# SchematicTensometr.net
KiCad netlist of a schematic drawn in Altium Designer
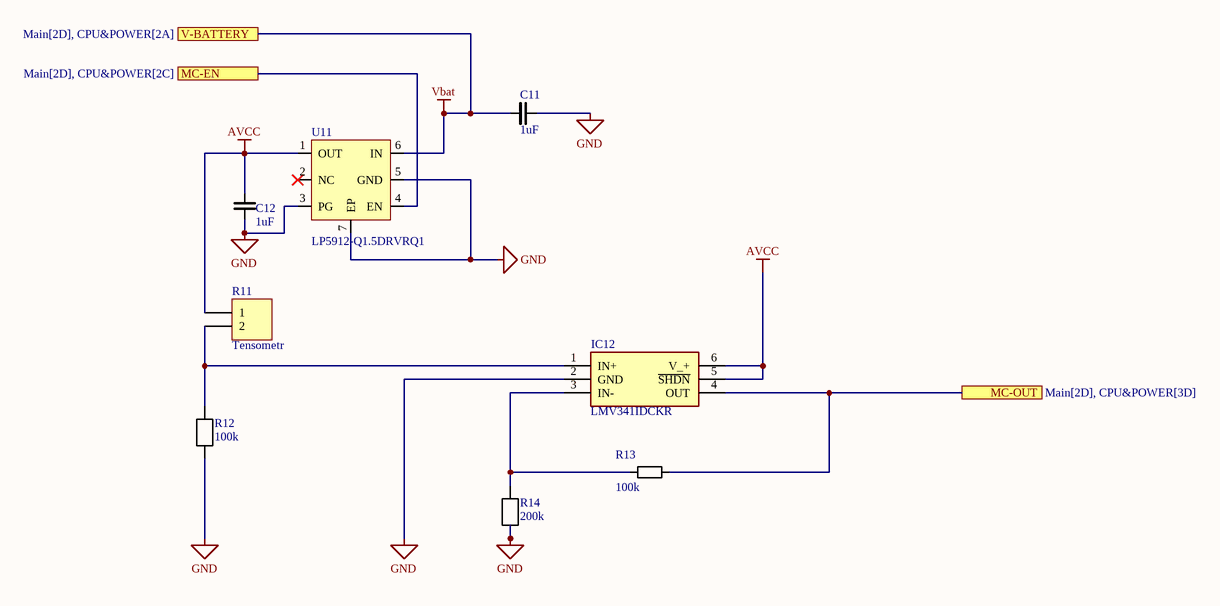
[diagram p0: SchematicTensometr.SchDoc]

(export (version "E")
  (design (tool "Eeschema 10.0.6"))
  (components
    (comp (ref "C11")
      (value "1uF")
      (footprint "0402_CAP")
      (description "Ceramic capacitor")
      (libsource (lib "Cap") (part "Cap"))
    )
    (comp (ref "C12")
      (value "1uF")
      (footprint "0402_CAP")
      (description "Ceramic capacitor")
      (libsource (lib "") (part "Cap_1"))
    )
    (comp (ref "IC12")
      (value "LMV341IDCKR")
      (footprint "SOT65P210X110-6N_m")
      (description "Integrated Circuit")
      (fields (field (name "MOUSER PART NUMBER") "595-LMV341IDCKR"))
      (libsource (lib "*") (part "LMV341IDCKR"))
    )
    (comp (ref "R11")
      (value "Tensometr")
      (footprint "HDR1X2")
      (description "Header, 2-Pin")
      (fields (field (name "PUBLISHER") "Altium Limited"))
      (libsource (lib "Miscellaneous Connectors") (part "Header 2"))
    )
    (comp (ref "R12") (value "100k") (footprint "0402_RES") (libsource (lib "Zad1") (part "Resistor")))
    (comp (ref "R13")
      (value "100k")
      (footprint "0402_RES")
      (description "Resistor")
      (libsource (lib "RES") (part "RES"))
    )
    (comp (ref "R14") (value "200k") (footprint "0402_RES") (libsource (lib "Zad1") (part "Resistor")))
    (comp (ref "U11")
      (value "LP5912-Q1.5DRVRQ1")
      (footprint "SON65P200X200X80-7N_m")
      (libsource (lib "parts1") (part "STAB"))
    )
  )
  (nets
    (net (code "1") (name "/MC-EN") (class "Default")
      (node (ref "U11") (pin "4") (pinfunction "EN_4") (pintype "passive"))
    )
    (net (code "2") (name "/MC-OUT") (class "Default")
      (node (ref "IC12") (pin "4") (pinfunction "OUT_4") (pintype "passive"))
      (node (ref "R13") (pin "2") (pinfunction "2_2") (pintype "passive"))
    )
    (net (code "3") (name "AVCC") (class "Default")
      (node (ref "C12") (pin "2") (pinfunction "2_2") (pintype "passive"))
      (node (ref "IC12") (pin "5") (pinfunction "~{SHDN}_5") (pintype "passive"))
      (node (ref "IC12") (pin "6") (pinfunction "V_+_6") (pintype "passive"))
      (node (ref "R11") (pin "1") (pinfunction "1_1") (pintype "passive"))
      (node (ref "U11") (pin "1") (pinfunction "OUT_1") (pintype "passive"))
    )
    (net (code "4") (name "GND") (class "Default")
      (node (ref "C11") (pin "1") (pinfunction "1_1") (pintype "passive"))
      (node (ref "C12") (pin "1") (pinfunction "1_1") (pintype "passive"))
      (node (ref "IC12") (pin "2") (pinfunction "GND_2") (pintype "passive"))
      (node (ref "R12") (pin "2") (pintype "passive"))
      (node (ref "R14") (pin "2") (pintype "passive"))
      (node (ref "U11") (pin "3") (pinfunction "PG_3") (pintype "passive"))
      (node (ref "U11") (pin "5") (pinfunction "GND_5") (pintype "passive"))
      (node (ref "U11") (pin "7") (pinfunction "EP_7") (pintype "passive"))
    )
    (net (code "5") (name "Net-(IC12-IN+)") (class "Default")
      (node (ref "IC12") (pin "1") (pinfunction "IN+_1") (pintype "passive"))
      (node (ref "R11") (pin "2") (pinfunction "2_2") (pintype "passive"))
      (node (ref "R12") (pin "1") (pintype "passive"))
    )
    (net (code "6") (name "Net-(IC12-IN-)") (class "Default")
      (node (ref "IC12") (pin "3") (pinfunction "IN-_3") (pintype "passive"))
      (node (ref "R13") (pin "1") (pinfunction "1_1") (pintype "passive"))
      (node (ref "R14") (pin "1") (pintype "passive"))
    )
    (net (code "7") (name "Vbat") (class "Default")
      (node (ref "C11") (pin "2") (pinfunction "2_2") (pintype "passive"))
      (node (ref "U11") (pin "6") (pinfunction "IN_6") (pintype "passive"))
    )
    (net (code "8") (name "unconnected-(U11-NC-Pad2)") (class "Default")
      (node (ref "U11") (pin "2") (pinfunction "NC_2") (pintype "passive+no_connect"))
    )
  )
)
